# StackLightMonitor.net
KiCad netlist of a schematic drawn in EAGLE
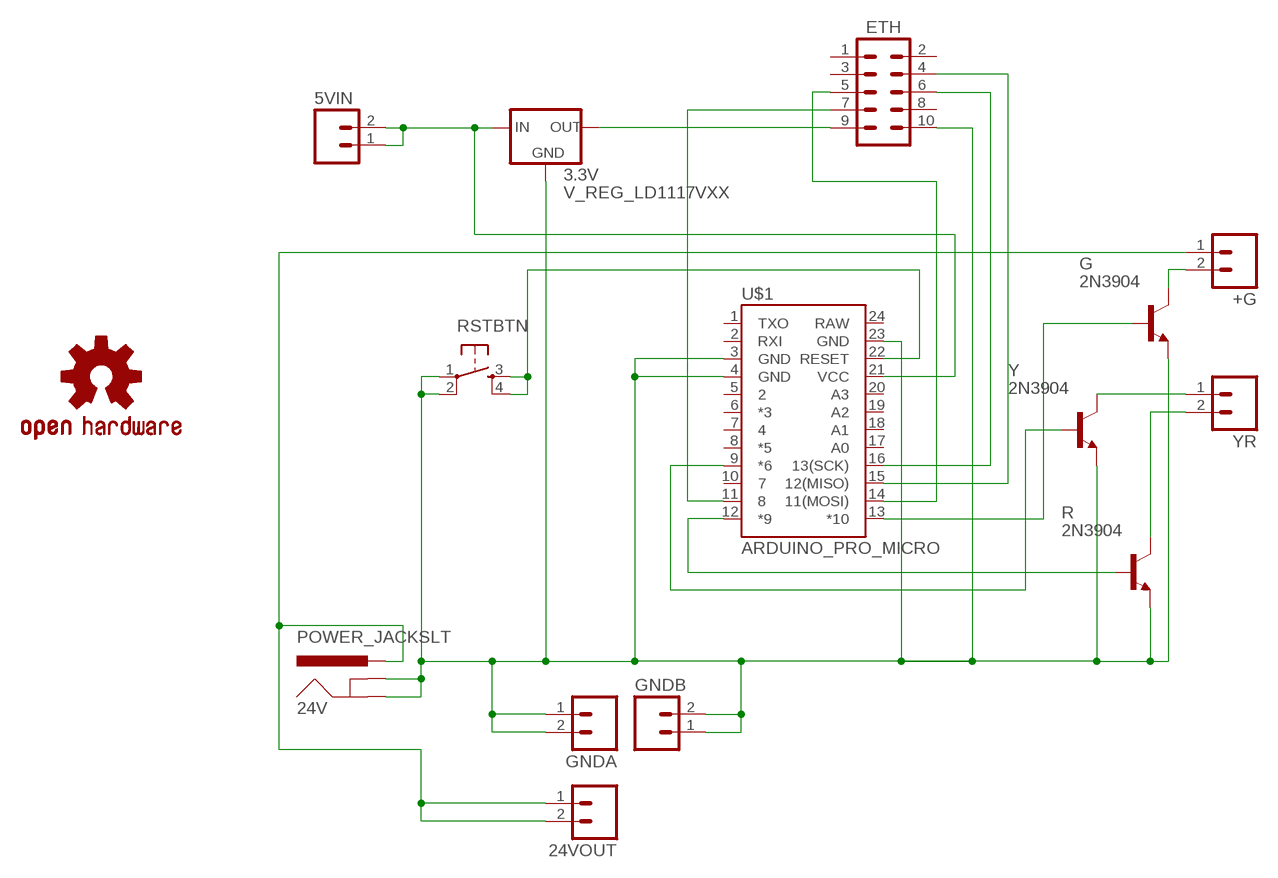
[diagram p0: schematic, sheet 1]

(export (version "E")
  (design (tool "Eeschema 10.0.6"))
  (components
    (comp (ref "+G")
      (value "M025MM")
      (footprint "eagle-import:SCREWTERMINAL-5MM-2")
      (libsource (lib "eagle-import") (part "M025MM"))
    )
    (comp (ref "3.3V")
      (value "V_REG_LD1117VXX")
      (footprint "eagle-import:78XXL")
      (libsource (lib "eagle-import") (part "V_REG_LD1117VXX"))
    )
    (comp (ref "5VIN")
      (value "M02PTH")
      (footprint "eagle-import:1X02")
      (libsource (lib "eagle-import") (part "M02PTH"))
    )
    (comp (ref "24V")
      (value "POWER_JACKSLT")
      (footprint "eagle-import:POWER_JACK_SLOT")
      (libsource (lib "eagle-import") (part "POWER_JACKSLT"))
    )
    (comp (ref "24VOUT")
      (value "M02PTH")
      (footprint "eagle-import:1X02")
      (libsource (lib "eagle-import") (part "M02PTH"))
    )
    (comp (ref "ETH")
      (value "M05X2PTH")
      (footprint "eagle-import:AVR_ICSP")
      (libsource (lib "eagle-import") (part "M05X2PTH"))
    )
    (comp (ref "G")
      (value "2N3904")
      (footprint "eagle-import:TO92")
      (libsource (lib "eagle-import") (part "2N3904"))
    )
    (comp (ref "GNDA")
      (value "M02PTH")
      (footprint "eagle-import:1X02")
      (libsource (lib "eagle-import") (part "M02PTH"))
    )
    (comp (ref "GNDB")
      (value "M02PTH")
      (footprint "eagle-import:1X02")
      (libsource (lib "eagle-import") (part "M02PTH"))
    )
    (comp (ref "LOGO1")
      (value "OSHW-LOGOL")
      (footprint "eagle-import:OSHW-LOGO-L")
      (libsource (lib "eagle-import") (part "OSHW-LOGOL"))
    )
    (comp (ref "R")
      (value "2N3904")
      (footprint "eagle-import:TO92")
      (libsource (lib "eagle-import") (part "2N3904"))
    )
    (comp (ref "RSTBTN")
      (value "TAC_SWITCHPTH")
      (footprint "eagle-import:TACTILE-PTH")
      (libsource (lib "eagle-import") (part "TAC_SWITCHPTH"))
    )
    (comp (ref "U$1")
      (value "ARDUINO_PRO_MICRO")
      (footprint "eagle-import:ARDUINO_PRO_MICRO")
      (libsource (lib "eagle-import") (part "ARDUINO_PRO_MICRO"))
    )
    (comp (ref "Y")
      (value "2N3904")
      (footprint "eagle-import:TO92")
      (libsource (lib "eagle-import") (part "2N3904"))
    )
    (comp (ref "YR")
      (value "M025MM")
      (footprint "eagle-import:SCREWTERMINAL-5MM-2")
      (libsource (lib "eagle-import") (part "M025MM"))
    )
  )
  (nets
    (net (code "1") (name "Net-(+G-Pad1)") (class "Default")
      (node (ref "+G") (pin "1") (pinfunction "1_1") (pintype "passive"))
      (node (ref "24V") (pin "PWR") (pinfunction "PWR_PWR") (pintype "bidirectional"))
      (node (ref "24VOUT") (pin "1") (pinfunction "1_1") (pintype "passive"))
      (node (ref "24VOUT") (pin "2") (pinfunction "2_2") (pintype "passive"))
    )
    (net (code "2") (name "Net-(3.3V-IN)") (class "Default")
      (node (ref "3.3V") (pin "OUT") (pinfunction "IN_OUT") (pintype "input"))
      (node (ref "5VIN") (pin "1") (pinfunction "1_1") (pintype "passive"))
      (node (ref "5VIN") (pin "2") (pinfunction "2_2") (pintype "passive"))
      (node (ref "U$1") (pin "21") (pinfunction "VCC_21") (pintype "bidirectional"))
    )
    (net (code "3") (name "Net-(3.3V-OUT)") (class "Default")
      (node (ref "3.3V") (pin "GND") (pinfunction "OUT_GND") (pintype "passive"))
      (node (ref "ETH") (pin "9") (pinfunction "9_9") (pintype "passive"))
    )
    (net (code "4") (name "Net-(24V-GND)") (class "Default")
      (node (ref "24V") (pin "GND@1") (pinfunction "GNDBREAK_GND@1") (pintype "bidirectional"))
      (node (ref "24V") (pin "GND@2") (pinfunction "GND_GND@2") (pintype "bidirectional"))
      (node (ref "3.3V") (pin "IN") (pinfunction "GND_IN") (pintype "input"))
      (node (ref "ETH") (pin "10") (pinfunction "10_10") (pintype "passive"))
      (node (ref "G") (pin "3") (pinfunction "E_3") (pintype "passive"))
      (node (ref "GNDA") (pin "1") (pinfunction "1_1") (pintype "passive"))
      (node (ref "GNDA") (pin "2") (pinfunction "2_2") (pintype "passive"))
      (node (ref "GNDB") (pin "1") (pinfunction "1_1") (pintype "passive"))
      (node (ref "GNDB") (pin "2") (pinfunction "2_2") (pintype "passive"))
      (node (ref "R") (pin "3") (pinfunction "E_3") (pintype "passive"))
      (node (ref "RSTBTN") (pin "1") (pinfunction "1_1") (pintype "passive"))
      (node (ref "RSTBTN") (pin "2") (pinfunction "2_2") (pintype "passive"))
      (node (ref "U$1") (pin "23") (pinfunction "GND_23") (pintype "bidirectional"))
      (node (ref "U$1") (pin "3") (pinfunction "GND_3") (pintype "bidirectional"))
      (node (ref "U$1") (pin "4") (pinfunction "GND_4") (pintype "bidirectional"))
      (node (ref "Y") (pin "3") (pinfunction "E_3") (pintype "passive"))
    )
    (net (code "5") (name "Net-(G-B)") (class "Default")
      (node (ref "G") (pin "2") (pinfunction "B_2") (pintype "passive"))
      (node (ref "U$1") (pin "13") (pinfunction "*10_13") (pintype "bidirectional"))
    )
    (net (code "6") (name "Net-(G-C)") (class "Default")
      (node (ref "+G") (pin "2") (pinfunction "2_2") (pintype "passive"))
      (node (ref "G") (pin "1") (pinfunction "C_1") (pintype "passive"))
    )
    (net (code "7") (name "Net-(R-B)") (class "Default")
      (node (ref "R") (pin "2") (pinfunction "B_2") (pintype "passive"))
      (node (ref "U$1") (pin "12") (pinfunction "*9_12") (pintype "bidirectional"))
    )
    (net (code "8") (name "Net-(R-C)") (class "Default")
      (node (ref "R") (pin "1") (pinfunction "C_1") (pintype "passive"))
      (node (ref "YR") (pin "2") (pinfunction "2_2") (pintype "passive"))
    )
    (net (code "9") (name "Net-(U$1-*6)") (class "Default")
      (node (ref "U$1") (pin "9") (pinfunction "*6_9") (pintype "bidirectional"))
      (node (ref "Y") (pin "2") (pinfunction "B_2") (pintype "passive"))
    )
    (net (code "10") (name "Net-(U$1-8)") (class "Default")
      (node (ref "ETH") (pin "7") (pinfunction "7_7") (pintype "passive"))
      (node (ref "U$1") (pin "11") (pinfunction "8_11") (pintype "bidirectional"))
    )
    (net (code "11") (name "Net-(U$1-11(MOSI))") (class "Default")
      (node (ref "ETH") (pin "5") (pinfunction "5_5") (pintype "passive"))
      (node (ref "U$1") (pin "14") (pinfunction "11(MOSI)_14") (pintype "bidirectional"))
    )
    (net (code "12") (name "Net-(U$1-12(MISO))") (class "Default")
      (node (ref "ETH") (pin "4") (pinfunction "4_4") (pintype "passive"))
      (node (ref "U$1") (pin "15") (pinfunction "12(MISO)_15") (pintype "bidirectional"))
    )
    (net (code "13") (name "Net-(U$1-13(SCK))") (class "Default")
      (node (ref "ETH") (pin "6") (pinfunction "6_6") (pintype "passive"))
      (node (ref "U$1") (pin "16") (pinfunction "13(SCK)_16") (pintype "bidirectional"))
    )
    (net (code "14") (name "Net-(U$1-RESET)") (class "Default")
      (node (ref "RSTBTN") (pin "3") (pinfunction "3_3") (pintype "passive"))
      (node (ref "RSTBTN") (pin "4") (pinfunction "4_4") (pintype "passive"))
      (node (ref "U$1") (pin "22") (pinfunction "RESET_22") (pintype "bidirectional"))
    )
    (net (code "15") (name "Net-(Y-C)") (class "Default")
      (node (ref "Y") (pin "1") (pinfunction "C_1") (pintype "passive"))
      (node (ref "YR") (pin "1") (pinfunction "1_1") (pintype "passive"))
    )
    (net (code "16") (name "unconnected-(ETH-Pad1)") (class "Default")
      (node (ref "ETH") (pin "1") (pinfunction "1_1") (pintype "passive"))
    )
    (net (code "17") (name "unconnected-(ETH-Pad2)") (class "Default")
      (node (ref "ETH") (pin "2") (pinfunction "2_2") (pintype "passive"))
    )
    (net (code "18") (name "unconnected-(ETH-Pad3)") (class "Default")
      (node (ref "ETH") (pin "3") (pinfunction "3_3") (pintype "passive"))
    )
    (net (code "19") (name "unconnected-(ETH-Pad8)") (class "Default")
      (node (ref "ETH") (pin "8") (pinfunction "8_8") (pintype "passive"))
    )
    (net (code "20") (name "unconnected-(U$1-*3-Pad6)") (class "Default")
      (node (ref "U$1") (pin "6") (pinfunction "*3_6") (pintype "bidirectional"))
    )
    (net (code "21") (name "unconnected-(U$1-*5-Pad8)") (class "Default")
      (node (ref "U$1") (pin "8") (pinfunction "*5_8") (pintype "bidirectional"))
    )
    (net (code "22") (name "unconnected-(U$1-2-Pad5)") (class "Default")
      (node (ref "U$1") (pin "5") (pinfunction "2_5") (pintype "bidirectional"))
    )
    (net (code "23") (name "unconnected-(U$1-4-Pad7)") (class "Default")
      (node (ref "U$1") (pin "7") (pinfunction "4_7") (pintype "bidirectional"))
    )
    (net (code "24") (name "unconnected-(U$1-7-Pad10)") (class "Default")
      (node (ref "U$1") (pin "10") (pinfunction "7_10") (pintype "bidirectional"))
    )
    (net (code "25") (name "unconnected-(U$1-A0-Pad17)") (class "Default")
      (node (ref "U$1") (pin "17") (pinfunction "A0_17") (pintype "bidirectional"))
    )
    (net (code "26") (name "unconnected-(U$1-A1-Pad18)") (class "Default")
      (node (ref "U$1") (pin "18") (pinfunction "A1_18") (pintype "bidirectional"))
    )
    (net (code "27") (name "unconnected-(U$1-A2-Pad19)") (class "Default")
      (node (ref "U$1") (pin "19") (pinfunction "A2_19") (pintype "bidirectional"))
    )
    (net (code "28") (name "unconnected-(U$1-A3-Pad20)") (class "Default")
      (node (ref "U$1") (pin "20") (pinfunction "A3_20") (pintype "bidirectional"))
    )
    (net (code "29") (name "unconnected-(U$1-RAW-Pad24)") (class "Default")
      (node (ref "U$1") (pin "24") (pinfunction "RAW_24") (pintype "bidirectional"))
    )
    (net (code "30") (name "unconnected-(U$1-RXI-Pad2)") (class "Default")
      (node (ref "U$1") (pin "2") (pinfunction "RXI_2") (pintype "bidirectional"))
    )
    (net (code "31") (name "unconnected-(U$1-TXO-Pad1)") (class "Default")
      (node (ref "U$1") (pin "1") (pinfunction "TXO_1") (pintype "bidirectional"))
    )
  )
)
